# rear_light_connect.net
KiCad netlist of a schematic drawn in EAGLE
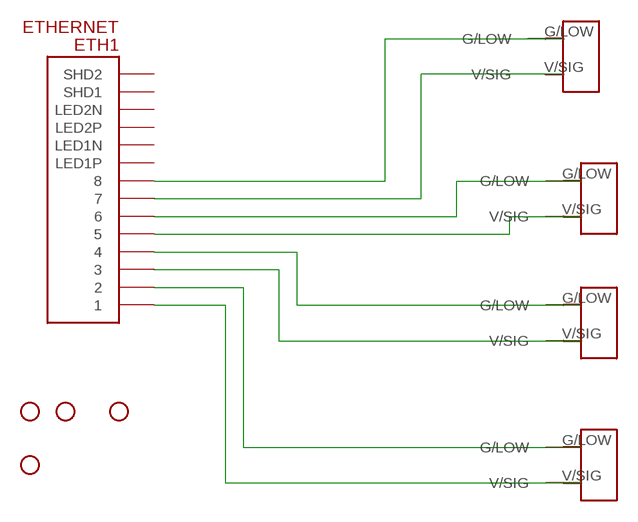
[diagram p0: schematic, sheet 1]

(export (version "E")
  (design (tool "Eeschema 10.0.6"))
  (components
    (comp (ref "ETH1")
      (value "ETHERNET")
      (footprint "eagle-import:A122645-ND")
      (libsource (lib "eagle-import") (part "ETHERNET"))
    )
    (comp (ref "H1")
      (value "STAND-OFF")
      (footprint "eagle-import:STAND-OFF")
      (libsource (lib "eagle-import") (part "STAND-OFF"))
    )
    (comp (ref "H2")
      (value "STAND-OFF")
      (footprint "eagle-import:STAND-OFF")
      (libsource (lib "eagle-import") (part "STAND-OFF"))
    )
    (comp (ref "H3")
      (value "STAND-OFF")
      (footprint "eagle-import:STAND-OFF")
      (libsource (lib "eagle-import") (part "STAND-OFF"))
    )
    (comp (ref "H4")
      (value "STAND-OFF")
      (footprint "eagle-import:STAND-OFF")
      (libsource (lib "eagle-import") (part "STAND-OFF"))
    )
    (comp (ref "L_DRIVE")
      (value "2_PIN_TECONNECTOR")
      (footprint "eagle-import:2_PIN_CONNECT")
      (libsource (lib "eagle-import") (part "2_PIN_TECONNECTOR"))
    )
    (comp (ref "L_SIG")
      (value "2_PIN_TECONNECTOR")
      (footprint "eagle-import:2_PIN_CONNECT")
      (libsource (lib "eagle-import") (part "2_PIN_TECONNECTOR"))
    )
    (comp (ref "R-DRIVE")
      (value "2_PIN_TECONNECTOR")
      (footprint "eagle-import:2_PIN_CONNECT")
      (libsource (lib "eagle-import") (part "2_PIN_TECONNECTOR"))
    )
    (comp (ref "R_SIG")
      (value "2_PIN_TECONNECTOR")
      (footprint "eagle-import:2_PIN_CONNECT")
      (libsource (lib "eagle-import") (part "2_PIN_TECONNECTOR"))
    )
  )
  (nets
    (net (code "1") (name "Net-(ETH1-1)") (class "Default")
      (node (ref "ETH1") (pin "P$1") (pinfunction "1_P$1") (pintype "bidirectional"))
      (node (ref "R-DRIVE") (pin "V/SIG") (pinfunction "V/SIG_V/SIG") (pintype "bidirectional"))
    )
    (net (code "2") (name "Net-(ETH1-2)") (class "Default")
      (node (ref "ETH1") (pin "P$2") (pinfunction "2_P$2") (pintype "bidirectional"))
      (node (ref "R-DRIVE") (pin "G/LOW") (pinfunction "G/LOW_G/LOW") (pintype "bidirectional"))
    )
    (net (code "3") (name "Net-(ETH1-3)") (class "Default")
      (node (ref "ETH1") (pin "P$3") (pinfunction "3_P$3") (pintype "bidirectional"))
      (node (ref "L_DRIVE") (pin "V/SIG") (pinfunction "V/SIG_V/SIG") (pintype "bidirectional"))
    )
    (net (code "4") (name "Net-(ETH1-4)") (class "Default")
      (node (ref "ETH1") (pin "P$4") (pinfunction "4_P$4") (pintype "bidirectional"))
      (node (ref "L_DRIVE") (pin "G/LOW") (pinfunction "G/LOW_G/LOW") (pintype "bidirectional"))
    )
    (net (code "5") (name "Net-(ETH1-5)") (class "Default")
      (node (ref "ETH1") (pin "P$5") (pinfunction "5_P$5") (pintype "bidirectional"))
      (node (ref "R_SIG") (pin "V/SIG") (pinfunction "V/SIG_V/SIG") (pintype "bidirectional"))
    )
    (net (code "6") (name "Net-(ETH1-6)") (class "Default")
      (node (ref "ETH1") (pin "P$6") (pinfunction "6_P$6") (pintype "bidirectional"))
      (node (ref "R_SIG") (pin "G/LOW") (pinfunction "G/LOW_G/LOW") (pintype "bidirectional"))
    )
    (net (code "7") (name "Net-(ETH1-7)") (class "Default")
      (node (ref "ETH1") (pin "P$7") (pinfunction "7_P$7") (pintype "bidirectional"))
      (node (ref "L_SIG") (pin "V/SIG") (pinfunction "V/SIG_V/SIG") (pintype "bidirectional"))
    )
    (net (code "8") (name "Net-(ETH1-8)") (class "Default")
      (node (ref "ETH1") (pin "P$8") (pinfunction "8_P$8") (pintype "bidirectional"))
      (node (ref "L_SIG") (pin "G/LOW") (pinfunction "G/LOW_G/LOW") (pintype "bidirectional"))
    )
    (net (code "9") (name "unconnected-(ETH1-LED1N-PadP$9)") (class "Default")
      (node (ref "ETH1") (pin "P$9") (pinfunction "LED1N_P$9") (pintype "bidirectional"))
    )
    (net (code "10") (name "unconnected-(ETH1-LED1P-PadP$10)") (class "Default")
      (node (ref "ETH1") (pin "P$10") (pinfunction "LED1P_P$10") (pintype "bidirectional"))
    )
    (net (code "11") (name "unconnected-(ETH1-LED2N-PadP$11)") (class "Default")
      (node (ref "ETH1") (pin "P$11") (pinfunction "LED2N_P$11") (pintype "bidirectional"))
    )
    (net (code "12") (name "unconnected-(ETH1-LED2P-PadP$12)") (class "Default")
      (node (ref "ETH1") (pin "P$12") (pinfunction "LED2P_P$12") (pintype "bidirectional"))
    )
    (net (code "13") (name "unconnected-(ETH1-SHD1-PadP$13)") (class "Default")
      (node (ref "ETH1") (pin "P$13") (pinfunction "SHD1_P$13") (pintype "bidirectional"))
    )
    (net (code "14") (name "unconnected-(ETH1-SHD2-PadP$14)") (class "Default")
      (node (ref "ETH1") (pin "P$14") (pinfunction "SHD2_P$14") (pintype "bidirectional"))
    )
  )
)
